# input_output.net
KiCad netlist of a schematic drawn in Altium Designer
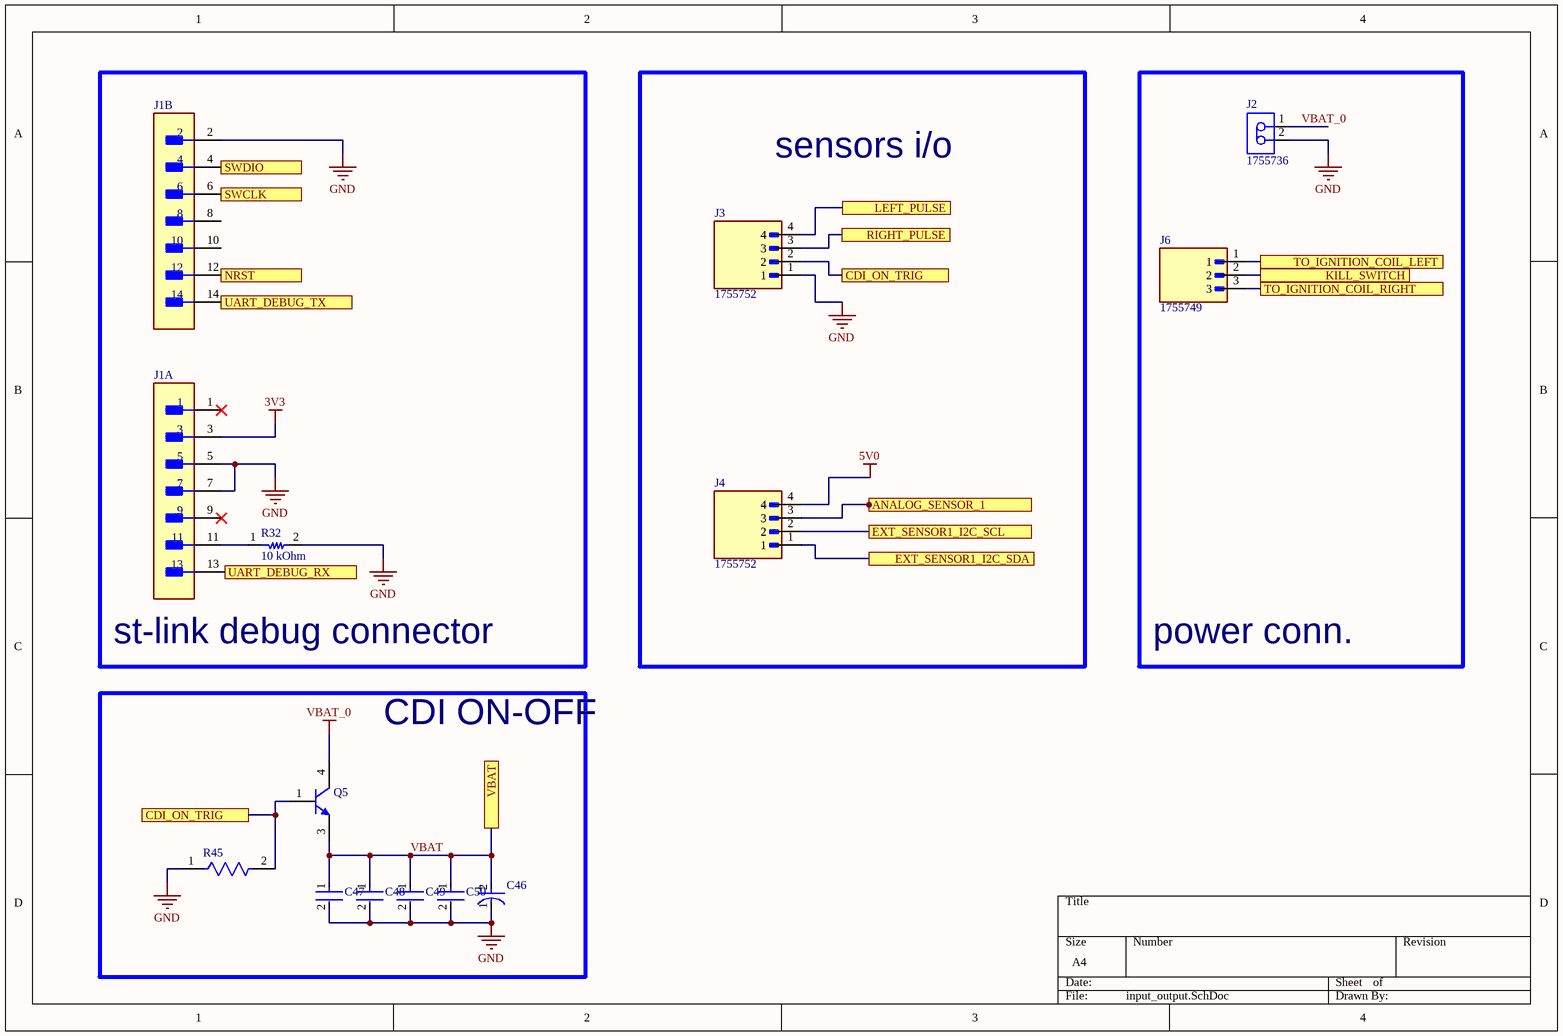
[diagram p0: input_output.SchDoc]

(export (version "E")
  (design (tool "Eeschema 10.0.6"))
  (components
    (comp (ref "C46")
      (value "EEEFT1E471AP")
      (footprint "FP-FTF-MFG")
      (description "CAP ALUM 470UF 20% 25V SMD")
      (fields (field (name "VOLTAGE") "25V") (field (name "TOLERANCE") "20%"))
      (libsource (lib "Altium Content Vault") (part "a00bbbee19879c290e62620ae7e47b1"))
    )
    (comp (ref "C47")
      (value "C1206X104J3GACTU")
      (footprint "FP-C1206X104J3GACTU-MFG")
      (description "CAP CER 0.1UF 25V C0G/NP0 1206")
      (libsource (lib "Altium Content Vault") (part "b4654b650e69147ec39a6b967a45e02"))
    )
    (comp (ref "C48")
      (value "C1206X104J3GACTU")
      (footprint "FP-C1206X104J3GACTU-MFG")
      (description "CAP CER 0.1UF 25V C0G/NP0 1206")
      (libsource (lib "Altium Content Vault") (part "b4654b650e69147ec39a6b967a45e02"))
    )
    (comp (ref "C49")
      (value "C1206X104J3GACTU")
      (footprint "FP-C1206X104J3GACTU-MFG")
      (description "CAP CER 0.1UF 25V C0G/NP0 1206")
      (libsource (lib "Altium Content Vault") (part "b4654b650e69147ec39a6b967a45e02"))
    )
    (comp (ref "C50")
      (value "C1206X104J3GACTU")
      (footprint "FP-C1206X104J3GACTU-MFG")
      (description "CAP CER 0.1UF 25V C0G/NP0 1206")
      (libsource (lib "Altium Content Vault") (part "b4654b650e69147ec39a6b967a45e02"))
    )
    (comp (ref "J1")
      (value "FTSH-107-01-F-DV-K")
      (footprint "FP-FTSH-107-01-F-DV-K-MFG")
      (description "CONN HEADER SMD 14POS 1.27MM")
      (libsource (lib "Altium Content Vault") (part "ab214579d66ef07f87fa9c6f4e4f9ab"))
    )
    (comp (ref "J2")
      (value "1755736")
      (footprint "PHOE-1755736-2_V")
      (description "Male Header, Pitch 5.08 mm, 1 x 2 Postion, Height 12 mm, Tail Length 3.9 mm, RoHS, Bulk")
      (fields (field (name "MANUFACTURER") "Phoenix Contact"))
      (libsource (lib "Altium Content Vault") (part "CN-2P-F-QF2"))
    )
    (comp (ref "J3")
      (value "1755752")
      (footprint "PHOENIX_1755752")
      (libsource (lib "1755752") (part "1755752"))
    )
    (comp (ref "J4")
      (value "1755752")
      (footprint "PHOENIX_1755752")
      (libsource (lib "1755752") (part "1755752"))
    )
    (comp (ref "J6")
      (value "1755749")
      (footprint "PHOENIX_1755749")
      (libsource (lib "1755749") (part "1755749"))
    )
    (comp (ref "Q5")
      (value "MJD3055T4G")
      (footprint "ONSC-DPAK-3-369C-01_V")
      (description "Complementary Power Transistor, 3-Pin DPAK, Pb-Free, Tape and Reel")
      (fields (field (name "MANUFACTURER") "On Semiconductor"))
      (libsource (lib "Altium Content Vault") (part "ONSC-NPN-B1E3C4-3"))
    )
    (comp (ref "R32")
      (value "10 kOhm")
      (footprint "0603_FP")
      (fields (field (name "Comment") "Resistor_0603"))
      (libsource (lib "RC_sch") (part "Resistor_0603"))
    )
    (comp (ref "R45")
      (value "CRGP0805F10K")
      (footprint "FP-CRGP0805-IPC_C")
      (description "CRGP 0805 10K 1%")
      (fields
        (field (name "MANUFACTURER") "TE")
        (field (name "OCTOPART") "https://octopart.com/crgp0805f10k-te+connectivity-91018782")
      )
      (libsource (lib "Altium Content Vault") (part "1029c3af85768c4190bb7ad29bc67b5"))
    )
  )
  (nets
    (net (code "1") (name "/ANALOG_SENSOR_1") (class "Default")
      (node (ref "J4") (pin "3") (pinfunction "3_3") (pintype "passive"))
    )
    (net (code "2") (name "/CDI_ON_TRIG") (class "Default")
      (node (ref "J3") (pin "2") (pinfunction "2_2") (pintype "passive"))
      (node (ref "Q5") (pin "1") (pinfunction "B_1") (pintype "passive"))
      (node (ref "R45") (pin "2") (pinfunction "2_2") (pintype "passive"))
    )
    (net (code "3") (name "/EXT_SENSOR1_I2C_SCL") (class "Default")
      (node (ref "J4") (pin "2") (pinfunction "2_2") (pintype "passive"))
    )
    (net (code "4") (name "/EXT_SENSOR1_I2C_SDA") (class "Default")
      (node (ref "J4") (pin "1") (pinfunction "1_1") (pintype "passive"))
    )
    (net (code "5") (name "/KILL_SWITCH") (class "Default")
      (node (ref "J6") (pin "2") (pinfunction "2_2") (pintype "passive"))
    )
    (net (code "6") (name "/LEFT_PULSE") (class "Default")
      (node (ref "J3") (pin "4") (pinfunction "4_4") (pintype "passive"))
    )
    (net (code "7") (name "/NRST") (class "Default")
      (node (ref "J1") (pin "12") (pinfunction "12_12") (pintype "passive"))
    )
    (net (code "8") (name "/RIGHT_PULSE") (class "Default")
      (node (ref "J3") (pin "3") (pinfunction "3_3") (pintype "passive"))
    )
    (net (code "9") (name "/SWCLK") (class "Default")
      (node (ref "J1") (pin "6") (pinfunction "6_6") (pintype "passive"))
    )
    (net (code "10") (name "/SWDIO") (class "Default")
      (node (ref "J1") (pin "4") (pinfunction "4_4") (pintype "passive"))
    )
    (net (code "11") (name "/TO_IGNITION_COIL_LEFT") (class "Default")
      (node (ref "J6") (pin "1") (pinfunction "1_1") (pintype "passive"))
    )
    (net (code "12") (name "/TO_IGNITION_COIL_RIGHT") (class "Default")
      (node (ref "J6") (pin "3") (pinfunction "3_3") (pintype "passive"))
    )
    (net (code "13") (name "/UART_DEBUG_RX") (class "Default")
      (node (ref "J1") (pin "13") (pinfunction "13_13") (pintype "passive"))
    )
    (net (code "14") (name "/UART_DEBUG_TX") (class "Default")
      (node (ref "J1") (pin "14") (pinfunction "14_14") (pintype "passive"))
    )
    (net (code "15") (name "/VBAT") (class "Default")
      (node (ref "C46") (pin "2") (pinfunction "A_2") (pintype "passive"))
      (node (ref "C47") (pin "1") (pinfunction "1_1") (pintype "passive"))
      (node (ref "C48") (pin "1") (pinfunction "1_1") (pintype "passive"))
      (node (ref "C49") (pin "1") (pinfunction "1_1") (pintype "passive"))
      (node (ref "C50") (pin "1") (pinfunction "1_1") (pintype "passive"))
      (node (ref "Q5") (pin "3") (pinfunction "E_3") (pintype "passive"))
    )
    (net (code "16") (name "3V3") (class "Default")
      (node (ref "J1") (pin "3") (pinfunction "3_3") (pintype "passive"))
    )
    (net (code "17") (name "5V0") (class "Default")
      (node (ref "J4") (pin "4") (pinfunction "4_4") (pintype "passive"))
    )
    (net (code "18") (name "GND") (class "Default")
      (node (ref "C46") (pin "1") (pinfunction "C_1") (pintype "passive"))
      (node (ref "C47") (pin "2") (pinfunction "2_2") (pintype "passive"))
      (node (ref "C48") (pin "2") (pinfunction "2_2") (pintype "passive"))
      (node (ref "C49") (pin "2") (pinfunction "2_2") (pintype "passive"))
      (node (ref "C50") (pin "2") (pinfunction "2_2") (pintype "passive"))
      (node (ref "J1") (pin "2") (pinfunction "2_2") (pintype "passive"))
      (node (ref "J1") (pin "5") (pinfunction "5_5") (pintype "passive"))
      (node (ref "J1") (pin "7") (pinfunction "7_7") (pintype "passive"))
      (node (ref "J2") (pin "2") (pinfunction "2_2") (pintype "passive"))
      (node (ref "J3") (pin "1") (pinfunction "1_1") (pintype "passive"))
      (node (ref "R32") (pin "2") (pinfunction "2_2") (pintype "passive"))
      (node (ref "R45") (pin "1") (pinfunction "1_1") (pintype "passive"))
    )
    (net (code "19") (name "Net-(J1-Pad11)") (class "Default")
      (node (ref "J1") (pin "11") (pinfunction "11_11") (pintype "passive"))
      (node (ref "R32") (pin "1") (pinfunction "1_1") (pintype "passive"))
    )
    (net (code "20") (name "VBAT_0") (class "Default")
      (node (ref "J2") (pin "1") (pinfunction "1_1") (pintype "passive"))
      (node (ref "Q5") (pin "4") (pinfunction "C_4") (pintype "passive"))
    )
    (net (code "21") (name "unconnected-(J1-Pad1)") (class "Default")
      (node (ref "J1") (pin "1") (pinfunction "1_1") (pintype "passive+no_connect"))
    )
    (net (code "22") (name "unconnected-(J1-Pad8)") (class "Default")
      (node (ref "J1") (pin "8") (pinfunction "8_8") (pintype "passive"))
    )
    (net (code "23") (name "unconnected-(J1-Pad9)") (class "Default")
      (node (ref "J1") (pin "9") (pinfunction "9_9") (pintype "passive+no_connect"))
    )
    (net (code "24") (name "unconnected-(J1-Pad10)") (class "Default")
      (node (ref "J1") (pin "10") (pinfunction "10_10") (pintype "passive"))
    )
  )
)
